# zynq_bottom.net
KiCad netlist of a schematic drawn in Altium Designer
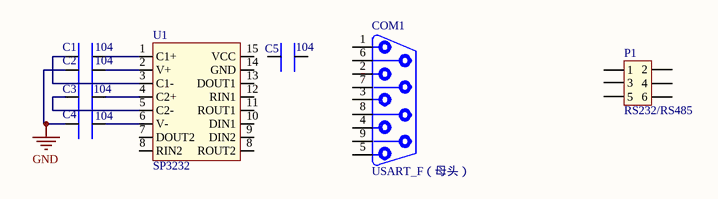
[diagram p0: zynq_bottom.SchDoc]

(export (version "E")
  (design (tool "Eeschema 10.0.6"))
  (components
    (comp (ref "C1")
      (value "104")
      (footprint "0603C")
      (libsource (lib "zynq_bottomSCHLIB") (part "0603C_104"))
    )
    (comp (ref "C2")
      (value "104")
      (footprint "0603C")
      (libsource (lib "zynq_bottomSCHLIB") (part "0603C_104"))
    )
    (comp (ref "C3")
      (value "104")
      (footprint "0603C")
      (libsource (lib "zynq_bottomSCHLIB") (part "0603C_104"))
    )
    (comp (ref "C4")
      (value "104")
      (footprint "0603C")
      (libsource (lib "zynq_bottomSCHLIB") (part "0603C_104"))
    )
    (comp (ref "C5")
      (value "104")
      (footprint "0603C")
      (libsource (lib "zynq_bottomSCHLIB") (part "0603C_104"))
    )
    (comp (ref "COM1")
      (value "USART_F（母头）")
      (footprint "DB9/S_A")
      (libsource (lib "zynq_bottomSCHLIB") (part "USART_F（母头）"))
    )
    (comp (ref "P1")
      (value "RS232/RS485")
      (footprint "HDR2.54-LI-2x3P")
      (libsource (lib "zynq_bottomSCHLIB") (part "RS232/RS485"))
    )
    (comp (ref "U1")
      (value "SP3232")
      (footprint "TSSOP16")
      (description "TSSOP16")
      (libsource (lib "zynq_bottomSCHLIB") (part "SP3232"))
    )
  )
  (nets
    (net (code "1") (name "GND") (class "Default")
      (node (ref "C2") (pin "1") (pinfunction "1_1") (pintype "passive"))
      (node (ref "C4") (pin "1") (pinfunction "1_1") (pintype "passive"))
    )
    (net (code "2") (name "Net-(U1-C1+)") (class "Default")
      (node (ref "C1") (pin "2") (pinfunction "2_2") (pintype "passive"))
      (node (ref "U1") (pin "1") (pinfunction "C1+_1") (pintype "passive"))
    )
    (net (code "3") (name "Net-(U1-C1-)") (class "Default")
      (node (ref "C1") (pin "1") (pinfunction "1_1") (pintype "passive"))
      (node (ref "U1") (pin "3") (pinfunction "C1-_3") (pintype "passive"))
    )
    (net (code "4") (name "Net-(U1-C2+)") (class "Default")
      (node (ref "C3") (pin "2") (pinfunction "2_2") (pintype "passive"))
      (node (ref "U1") (pin "4") (pinfunction "C2+_4") (pintype "passive"))
    )
    (net (code "5") (name "Net-(U1-C2-)") (class "Default")
      (node (ref "C3") (pin "1") (pinfunction "1_1") (pintype "passive"))
      (node (ref "U1") (pin "5") (pinfunction "C2-_5") (pintype "passive"))
    )
    (net (code "6") (name "Net-(U1-V+)") (class "Default")
      (node (ref "C2") (pin "2") (pinfunction "2_2") (pintype "passive"))
      (node (ref "U1") (pin "2") (pinfunction "V+_2") (pintype "passive"))
    )
    (net (code "7") (name "Net-(U1-V-)") (class "Default")
      (node (ref "C4") (pin "2") (pinfunction "2_2") (pintype "passive"))
      (node (ref "U1") (pin "6") (pinfunction "V-_6") (pintype "passive"))
    )
    (net (code "8") (name "unconnected-(C5-Pad1)") (class "Default")
      (node (ref "C5") (pin "1") (pinfunction "1_1") (pintype "passive"))
    )
    (net (code "9") (name "unconnected-(C5-Pad2)") (class "Default")
      (node (ref "C5") (pin "2") (pinfunction "2_2") (pintype "passive"))
    )
    (net (code "10") (name "unconnected-(COM1-Pad1)") (class "Default")
      (node (ref "COM1") (pin "1") (pinfunction "1_1") (pintype "passive"))
    )
    (net (code "11") (name "unconnected-(COM1-Pad2)") (class "Default")
      (node (ref "COM1") (pin "2") (pinfunction "2_2") (pintype "passive"))
    )
    (net (code "12") (name "unconnected-(COM1-Pad3)") (class "Default")
      (node (ref "COM1") (pin "3") (pinfunction "3_3") (pintype "passive"))
    )
    (net (code "13") (name "unconnected-(COM1-Pad4)") (class "Default")
      (node (ref "COM1") (pin "4") (pinfunction "4_4") (pintype "passive"))
    )
    (net (code "14") (name "unconnected-(COM1-Pad5)") (class "Default")
      (node (ref "COM1") (pin "5") (pinfunction "5_5") (pintype "passive"))
    )
    (net (code "15") (name "unconnected-(COM1-Pad6)") (class "Default")
      (node (ref "COM1") (pin "6") (pinfunction "6_6") (pintype "passive"))
    )
    (net (code "16") (name "unconnected-(COM1-Pad7)") (class "Default")
      (node (ref "COM1") (pin "7") (pinfunction "7_7") (pintype "passive"))
    )
    (net (code "17") (name "unconnected-(COM1-Pad8)") (class "Default")
      (node (ref "COM1") (pin "8") (pinfunction "8_8") (pintype "passive"))
    )
    (net (code "18") (name "unconnected-(COM1-Pad9)") (class "Default")
      (node (ref "COM1") (pin "9") (pinfunction "9_9") (pintype "passive"))
    )
    (net (code "19") (name "unconnected-(P1-Pad1)") (class "Default")
      (node (ref "P1") (pin "1") (pinfunction "1_1") (pintype "passive"))
    )
    (net (code "20") (name "unconnected-(P1-Pad2)") (class "Default")
      (node (ref "P1") (pin "2") (pinfunction "2_2") (pintype "passive"))
    )
    (net (code "21") (name "unconnected-(P1-Pad3)") (class "Default")
      (node (ref "P1") (pin "3") (pinfunction "3_3") (pintype "passive"))
    )
    (net (code "22") (name "unconnected-(P1-Pad4)") (class "Default")
      (node (ref "P1") (pin "4") (pinfunction "4_4") (pintype "passive"))
    )
    (net (code "23") (name "unconnected-(P1-Pad5)") (class "Default")
      (node (ref "P1") (pin "5") (pinfunction "5_5") (pintype "passive"))
    )
    (net (code "24") (name "unconnected-(P1-Pad6)") (class "Default")
      (node (ref "P1") (pin "6") (pinfunction "6_6") (pintype "passive"))
    )
    (net (code "25") (name "unconnected-(U1-DIN1-Pad10)") (class "Default")
      (node (ref "U1") (pin "10") (pinfunction "DIN1_10") (pintype "passive"))
    )
    (net (code "26") (name "unconnected-(U1-DIN2-Pad9)") (class "Default")
      (node (ref "U1") (pin "9") (pinfunction "DIN2_9") (pintype "passive"))
    )
    (net (code "27") (name "unconnected-(U1-DOUT1-Pad13)") (class "Default")
      (node (ref "U1") (pin "13") (pinfunction "DOUT1_13") (pintype "passive"))
    )
    (net (code "28") (name "unconnected-(U1-DOUT2-Pad7)") (class "Default")
      (node (ref "U1") (pin "7") (pinfunction "DOUT2_7") (pintype "passive"))
    )
    (net (code "29") (name "unconnected-(U1-GND-Pad14)") (class "Default")
      (node (ref "U1") (pin "14") (pinfunction "GND_14") (pintype "passive"))
    )
    (net (code "30") (name "unconnected-(U1-RIN1-Pad12)") (class "Default")
      (node (ref "U1") (pin "12") (pinfunction "RIN1_12") (pintype "passive"))
    )
    (net (code "31") (name "unconnected-(U1-RIN2-Pad8)") (class "Default")
      (node (ref "U1") (pin "8") (pinfunction "RIN2_8") (pintype "passive"))
    )
    (net (code "32") (name "unconnected-(U1-ROUT1-Pad11)") (class "Default")
      (node (ref "U1") (pin "11") (pinfunction "ROUT1_11") (pintype "passive"))
    )
    (net (code "33") (name "unconnected-(U1-ROUT2-Pad8)") (class "Default")
      (node (ref "U1") (pin "8") (pinfunction "ROUT2_8") (pintype "passive"))
    )
    (net (code "34") (name "unconnected-(U1-VCC-Pad15)") (class "Default")
      (node (ref "U1") (pin "15") (pinfunction "VCC_15") (pintype "passive"))
    )
  )
)
